# PI3523_EVAL_v2.net
KiCad netlist of a schematic drawn in EAGLE
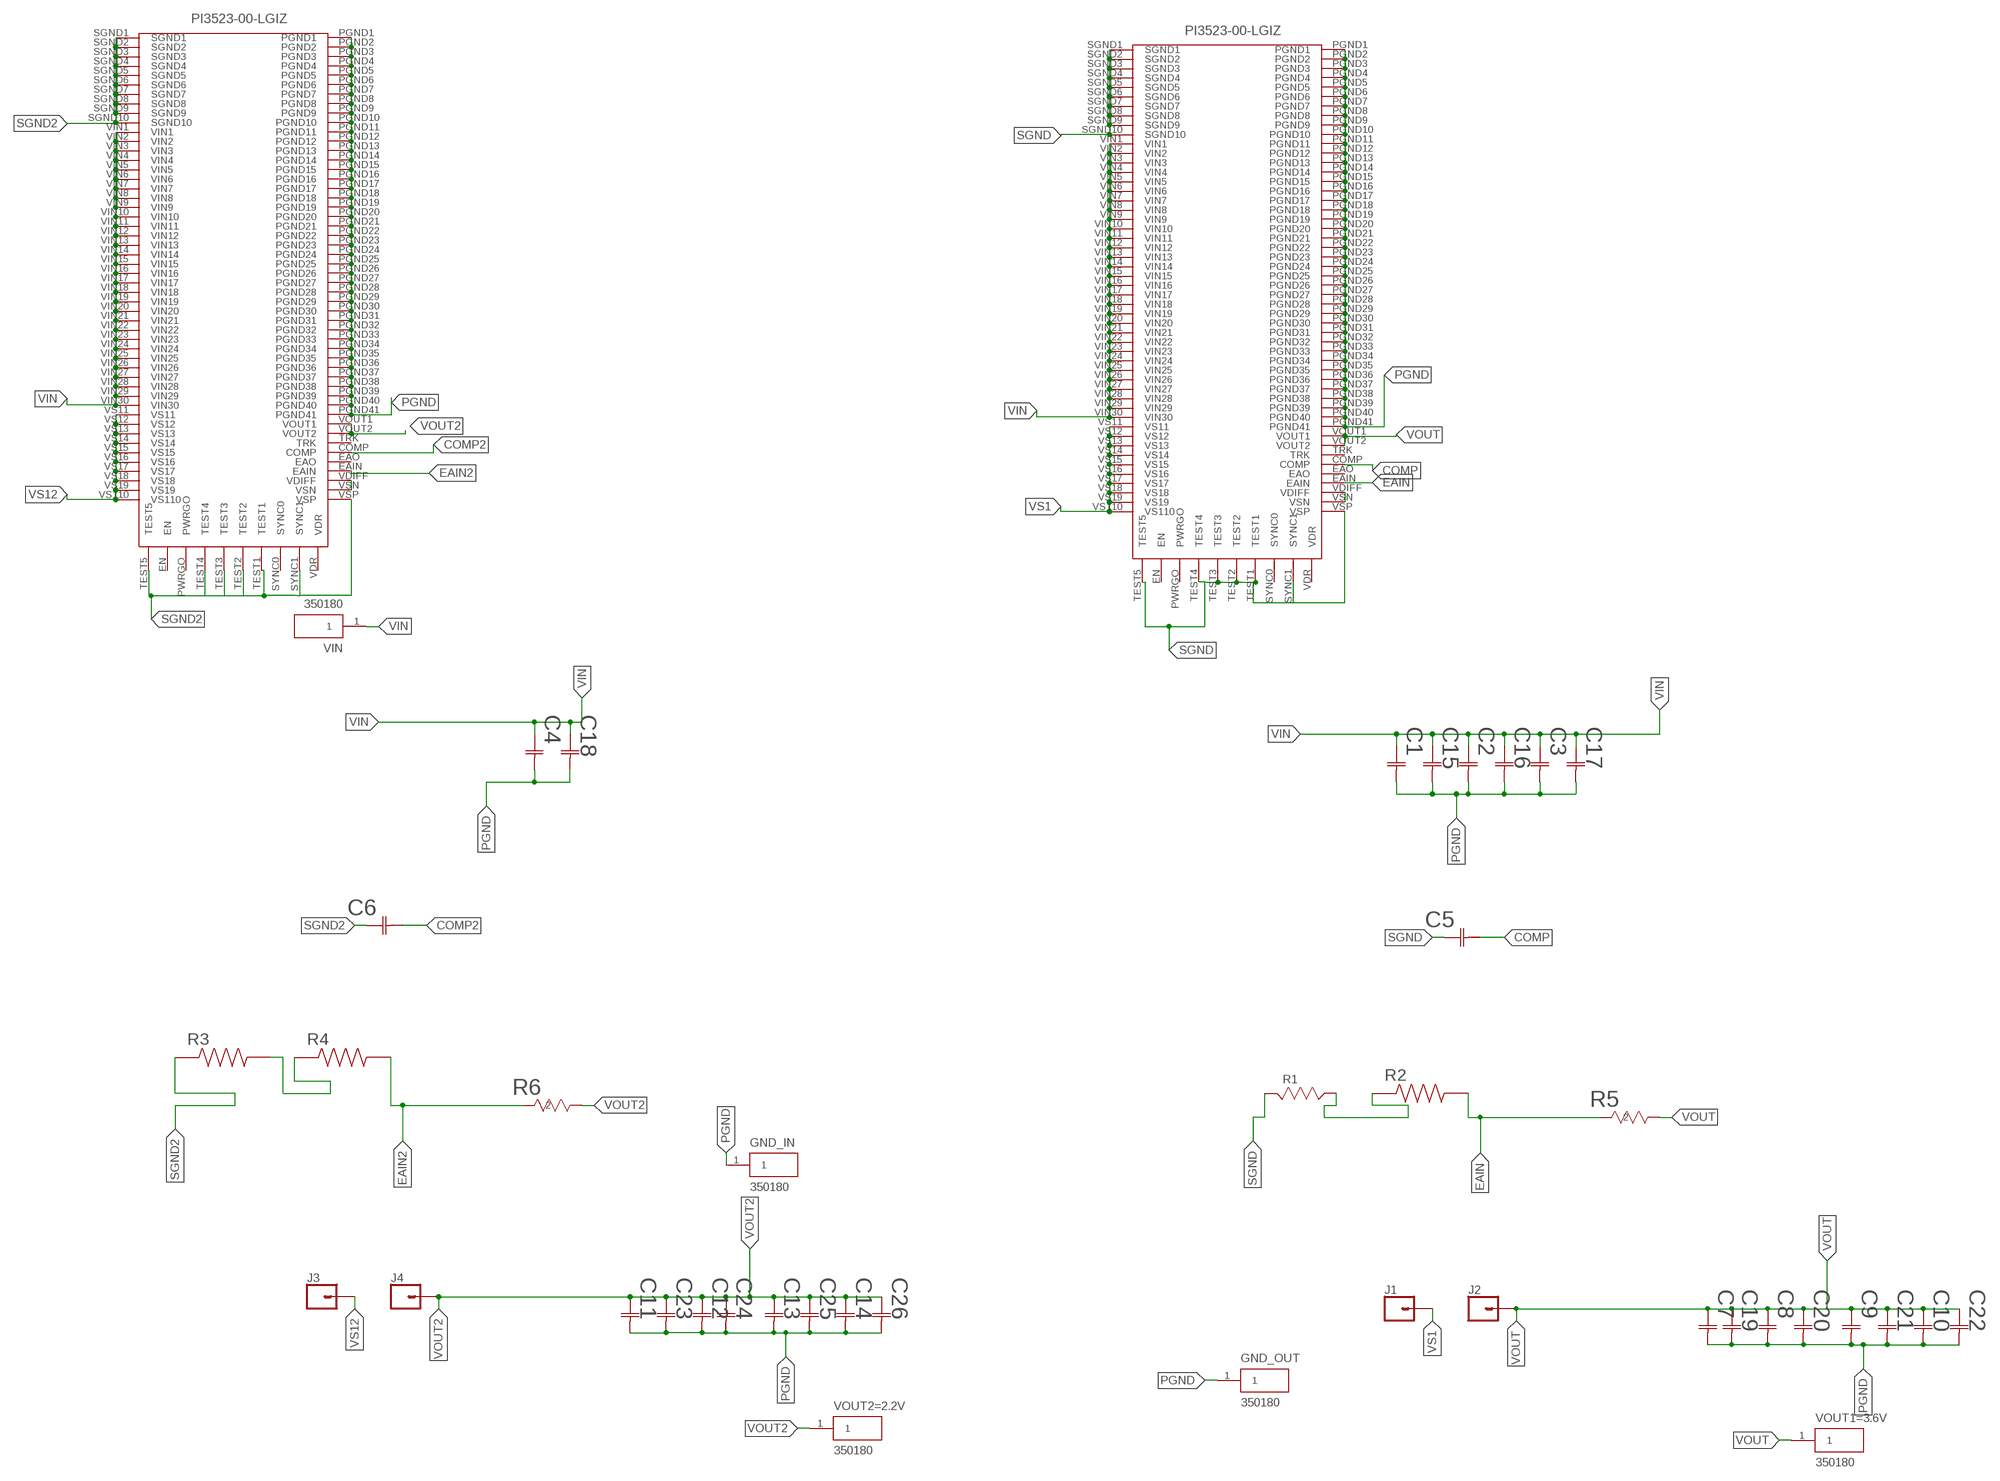
[diagram p0: schematic, sheet 1]

(export (version "E")
  (design (tool "Eeschema 10.0.6"))
  (components
    (comp (ref "C1")
      (value "GRM32ER72A225KA35L")
      (footprint "eagle-import:G-32_MUR")
      (fields (field (name "COPYRIGHT") "Copyright (C) 2015 Accelerated Designs. All rights reserved"))
      (libsource (lib "eagle-import") (part "GRM32ER72A225KA35L"))
    )
    (comp (ref "C2")
      (value "GRM32ER72A225KA35L")
      (footprint "eagle-import:G-32_MUR")
      (fields (field (name "COPYRIGHT") "Copyright (C) 2015 Accelerated Designs. All rights reserved"))
      (libsource (lib "eagle-import") (part "GRM32ER72A225KA35L"))
    )
    (comp (ref "C3")
      (value "GRM32ER72A225KA35L")
      (footprint "eagle-import:G-32_MUR")
      (fields (field (name "COPYRIGHT") "Copyright (C) 2015 Accelerated Designs. All rights reserved"))
      (libsource (lib "eagle-import") (part "GRM32ER72A225KA35L"))
    )
    (comp (ref "C4")
      (value "GRM32ER72A225KA35L")
      (footprint "eagle-import:G-32_MUR")
      (fields (field (name "COPYRIGHT") "Copyright (C) 2015 Accelerated Designs. All rights reserved"))
      (libsource (lib "eagle-import") (part "GRM32ER72A225KA35L"))
    )
    (comp (ref "C5")
      (value "C1608C0G2A472J080AC")
      (footprint "eagle-import:CAP_C1608_TDK")
      (fields (field (name "COPYRIGHT") "Copyright (C) 2018 Accelerated Designs. All rights reserved"))
      (libsource (lib "eagle-import") (part "C1608C0G2A472J080AC"))
    )
    (comp (ref "C6")
      (value "C1608C0G2A472J080AC")
      (footprint "eagle-import:CAP_C1608_TDK")
      (fields (field (name "COPYRIGHT") "Copyright (C) 2018 Accelerated Designs. All rights reserved"))
      (libsource (lib "eagle-import") (part "C1608C0G2A472J080AC"))
    )
    (comp (ref "C7")
      (value "GRM32EC80J107ME20L")
      (footprint "eagle-import:G-32_MUR")
      (fields (field (name "COPYRIGHT") "Copyright (C) 2015 Accelerated Designs. All rights reserved"))
      (libsource (lib "eagle-import") (part "GRM32EC80J107ME20L"))
    )
    (comp (ref "C8")
      (value "GRM32EC80J107ME20L")
      (footprint "eagle-import:G-32_MUR")
      (fields (field (name "COPYRIGHT") "Copyright (C) 2015 Accelerated Designs. All rights reserved"))
      (libsource (lib "eagle-import") (part "GRM32EC80J107ME20L"))
    )
    (comp (ref "C9")
      (value "GRM32EC80J107ME20L")
      (footprint "eagle-import:G-32_MUR")
      (fields (field (name "COPYRIGHT") "Copyright (C) 2015 Accelerated Designs. All rights reserved"))
      (libsource (lib "eagle-import") (part "GRM32EC80J107ME20L"))
    )
    (comp (ref "C10")
      (value "GRM32EC80J107ME20L")
      (footprint "eagle-import:G-32_MUR")
      (fields (field (name "COPYRIGHT") "Copyright (C) 2015 Accelerated Designs. All rights reserved"))
      (libsource (lib "eagle-import") (part "GRM32EC80J107ME20L"))
    )
    (comp (ref "C11")
      (value "GRM32EC80J107ME20L")
      (footprint "eagle-import:G-32_MUR")
      (fields (field (name "COPYRIGHT") "Copyright (C) 2015 Accelerated Designs. All rights reserved"))
      (libsource (lib "eagle-import") (part "GRM32EC80J107ME20L"))
    )
    (comp (ref "C12")
      (value "GRM32EC80J107ME20L")
      (footprint "eagle-import:G-32_MUR")
      (fields (field (name "COPYRIGHT") "Copyright (C) 2015 Accelerated Designs. All rights reserved"))
      (libsource (lib "eagle-import") (part "GRM32EC80J107ME20L"))
    )
    (comp (ref "C13")
      (value "GRM32EC80J107ME20L")
      (footprint "eagle-import:G-32_MUR")
      (fields (field (name "COPYRIGHT") "Copyright (C) 2015 Accelerated Designs. All rights reserved"))
      (libsource (lib "eagle-import") (part "GRM32EC80J107ME20L"))
    )
    (comp (ref "C14")
      (value "GRM32EC80J107ME20L")
      (footprint "eagle-import:G-32_MUR")
      (fields (field (name "COPYRIGHT") "Copyright (C) 2015 Accelerated Designs. All rights reserved"))
      (libsource (lib "eagle-import") (part "GRM32EC80J107ME20L"))
    )
    (comp (ref "C15")
      (value "GRM32ER72A225KA35L")
      (footprint "eagle-import:G-32_MUR")
      (fields (field (name "COPYRIGHT") "Copyright (C) 2015 Accelerated Designs. All rights reserved"))
      (libsource (lib "eagle-import") (part "GRM32ER72A225KA35L"))
    )
    (comp (ref "C16")
      (value "GRM32ER72A225KA35L")
      (footprint "eagle-import:G-32_MUR")
      (fields (field (name "COPYRIGHT") "Copyright (C) 2015 Accelerated Designs. All rights reserved"))
      (libsource (lib "eagle-import") (part "GRM32ER72A225KA35L"))
    )
    (comp (ref "C17")
      (value "GRM32ER72A225KA35L")
      (footprint "eagle-import:G-32_MUR")
      (fields (field (name "COPYRIGHT") "Copyright (C) 2015 Accelerated Designs. All rights reserved"))
      (libsource (lib "eagle-import") (part "GRM32ER72A225KA35L"))
    )
    (comp (ref "C18")
      (value "GRM32ER72A225KA35L")
      (footprint "eagle-import:G-32_MUR")
      (fields (field (name "COPYRIGHT") "Copyright (C) 2015 Accelerated Designs. All rights reserved"))
      (libsource (lib "eagle-import") (part "GRM32ER72A225KA35L"))
    )
    (comp (ref "C19")
      (value "GRM32EC80J107ME20L")
      (footprint "eagle-import:G-32_MUR")
      (fields (field (name "COPYRIGHT") "Copyright (C) 2015 Accelerated Designs. All rights reserved"))
      (libsource (lib "eagle-import") (part "GRM32EC80J107ME20L"))
    )
    (comp (ref "C20")
      (value "GRM32EC80J107ME20L")
      (footprint "eagle-import:G-32_MUR")
      (fields (field (name "COPYRIGHT") "Copyright (C) 2015 Accelerated Designs. All rights reserved"))
      (libsource (lib "eagle-import") (part "GRM32EC80J107ME20L"))
    )
    (comp (ref "C21")
      (value "GRM32EC80J107ME20L")
      (footprint "eagle-import:G-32_MUR")
      (fields (field (name "COPYRIGHT") "Copyright (C) 2015 Accelerated Designs. All rights reserved"))
      (libsource (lib "eagle-import") (part "GRM32EC80J107ME20L"))
    )
    (comp (ref "C22")
      (value "GRM32EC80J107ME20L")
      (footprint "eagle-import:G-32_MUR")
      (fields (field (name "COPYRIGHT") "Copyright (C) 2015 Accelerated Designs. All rights reserved"))
      (libsource (lib "eagle-import") (part "GRM32EC80J107ME20L"))
    )
    (comp (ref "C23")
      (value "GRM32EC80J107ME20L")
      (footprint "eagle-import:G-32_MUR")
      (fields (field (name "COPYRIGHT") "Copyright (C) 2015 Accelerated Designs. All rights reserved"))
      (libsource (lib "eagle-import") (part "GRM32EC80J107ME20L"))
    )
    (comp (ref "C24")
      (value "GRM32EC80J107ME20L")
      (footprint "eagle-import:G-32_MUR")
      (fields (field (name "COPYRIGHT") "Copyright (C) 2015 Accelerated Designs. All rights reserved"))
      (libsource (lib "eagle-import") (part "GRM32EC80J107ME20L"))
    )
    (comp (ref "C25")
      (value "GRM32EC80J107ME20L")
      (footprint "eagle-import:G-32_MUR")
      (fields (field (name "COPYRIGHT") "Copyright (C) 2015 Accelerated Designs. All rights reserved"))
      (libsource (lib "eagle-import") (part "GRM32EC80J107ME20L"))
    )
    (comp (ref "C26")
      (value "GRM32EC80J107ME20L")
      (footprint "eagle-import:G-32_MUR")
      (fields (field (name "COPYRIGHT") "Copyright (C) 2015 Accelerated Designs. All rights reserved"))
      (libsource (lib "eagle-import") (part "GRM32EC80J107ME20L"))
    )
    (comp (ref "GND_IN")
      (value "350180")
      (footprint "eagle-import:TE_350180")
      (fields (field (name "MF") "TE Connectivity"))
      (libsource (lib "eagle-import") (part "350180"))
    )
    (comp (ref "GND_OUT")
      (value "350180")
      (footprint "eagle-import:TE_350180")
      (fields (field (name "MF") "TE Connectivity"))
      (libsource (lib "eagle-import") (part "350180"))
    )
    (comp (ref "J1")
      (value "CONN_01")
      (footprint "eagle-import:1X01")
      (libsource (lib "eagle-import") (part "CONN_01"))
    )
    (comp (ref "J2")
      (value "CONN_01")
      (footprint "eagle-import:1X01")
      (libsource (lib "eagle-import") (part "CONN_01"))
    )
    (comp (ref "J3")
      (value "CONN_01")
      (footprint "eagle-import:1X01")
      (libsource (lib "eagle-import") (part "CONN_01"))
    )
    (comp (ref "J4")
      (value "CONN_01")
      (footprint "eagle-import:1X01")
      (libsource (lib "eagle-import") (part "CONN_01"))
    )
    (comp (ref "R1")
      (value "ERJ-3GEY0R00V")
      (footprint "eagle-import:RESC1608X55")
      (fields (field (name "MF") "Panasonic Electronic"))
      (libsource (lib "eagle-import") (part "ERJ-3GEY0R00V"))
    )
    (comp (ref "R2")
      (value "ERA-3APB911V")
      (footprint "eagle-import:RESC1608X55N")
      (fields (field (name "MF") "Panasonic"))
      (libsource (lib "eagle-import") (part "ERA-3APB911V"))
    )
    (comp (ref "R3")
      (value "ERJ-3BQJ3R6V")
      (footprint "eagle-import:RESC1608X55N")
      (fields (field (name "MF") "Panasonic"))
      (libsource (lib "eagle-import") (part "ERJ-3BQJ3R6V"))
    )
    (comp (ref "R4")
      (value "ERA-3AEB1961V")
      (footprint "eagle-import:RESC1608X55N")
      (fields (field (name "MF") "Panasonic"))
      (libsource (lib "eagle-import") (part "ERA-3AEB1961V"))
    )
    (comp (ref "R5")
      (value "RT0603BRE072K4L")
      (footprint "eagle-import:RC0603N_YAG")
      (libsource (lib "eagle-import") (part "RT0603BRE072K4L"))
    )
    (comp (ref "R6")
      (value "RT0603BRE072K4L")
      (footprint "eagle-import:RC0603N_YAG")
      (libsource (lib "eagle-import") (part "RT0603BRE072K4L"))
    )
    (comp (ref "U$1")
      (value "PI3523-00-LGIZ")
      (footprint "eagle-import:PI3523-00-LGIZ")
      (libsource (lib "eagle-import") (part "PI3523-00-LGIZ"))
    )
    (comp (ref "U$2")
      (value "PI3523-00-LGIZ")
      (footprint "eagle-import:PI3523-00-LGIZ")
      (libsource (lib "eagle-import") (part "PI3523-00-LGIZ"))
    )
    (comp (ref "VIN")
      (value "350180")
      (footprint "eagle-import:TE_350180")
      (fields (field (name "MF") "TE Connectivity"))
      (libsource (lib "eagle-import") (part "350180"))
    )
    (comp (ref "VOUT1=3.6V")
      (value "350180")
      (footprint "eagle-import:TE_350180")
      (fields (field (name "MF") "TE Connectivity"))
      (libsource (lib "eagle-import") (part "350180"))
    )
    (comp (ref "VOUT2=2.2V")
      (value "350180")
      (footprint "eagle-import:TE_350180")
      (fields (field (name "MF") "TE Connectivity"))
      (libsource (lib "eagle-import") (part "350180"))
    )
  )
  (nets
    (net (code "1") (name "COMP") (class "Default")
      (node (ref "C5") (pin "2") (pinfunction "2_2") (pintype "passive"))
      (node (ref "U$2") (pin "COMP") (pinfunction "COMP_COMP") (pintype "bidirectional"))
    )
    (net (code "2") (name "COMP2") (class "Default")
      (node (ref "C6") (pin "2") (pinfunction "2_2") (pintype "passive"))
      (node (ref "U$1") (pin "COMP") (pinfunction "COMP_COMP") (pintype "bidirectional"))
    )
    (net (code "3") (name "EAIN") (class "Default")
      (node (ref "R2") (pin "2") (pinfunction "2_2") (pintype "passive"))
      (node (ref "R5") (pin "2") (pinfunction "2_2") (pintype "passive"))
      (node (ref "U$2") (pin "EAIN") (pinfunction "EAIN_EAIN") (pintype "bidirectional"))
    )
    (net (code "4") (name "EAIN2") (class "Default")
      (node (ref "R4") (pin "2") (pinfunction "2_2") (pintype "passive"))
      (node (ref "R6") (pin "2") (pinfunction "2_2") (pintype "passive"))
      (node (ref "U$1") (pin "EAIN") (pinfunction "EAIN_EAIN") (pintype "bidirectional"))
    )
    (net (code "5") (name "Net-(R1-Pad2)") (class "Default")
      (node (ref "R1") (pin "2") (pinfunction "2_2") (pintype "passive"))
      (node (ref "R2") (pin "1") (pinfunction "1_1") (pintype "passive"))
    )
    (net (code "6") (name "Net-(R3-Pad2)") (class "Default")
      (node (ref "R3") (pin "2") (pinfunction "2_2") (pintype "passive"))
      (node (ref "R4") (pin "1") (pinfunction "1_1") (pintype "passive"))
    )
    (net (code "7") (name "Net-(U$1-PadVDIFF)") (class "Default")
      (node (ref "U$1") (pin "VDIFF") (pinfunction "VDIFF_VDIFF") (pintype "bidirectional"))
      (node (ref "U$1") (pin "VSN") (pinfunction "VSN_VSN") (pintype "bidirectional"))
    )
    (net (code "8") (name "Net-(U$2-PadVDIFF)") (class "Default")
      (node (ref "U$2") (pin "VDIFF") (pinfunction "VDIFF_VDIFF") (pintype "bidirectional"))
      (node (ref "U$2") (pin "VSN") (pinfunction "VSN_VSN") (pintype "bidirectional"))
    )
    (net (code "9") (name "PGND") (class "Default")
      (node (ref "C1") (pin "2") (pinfunction "2_2") (pintype "passive"))
      (node (ref "C10") (pin "2") (pinfunction "2_2") (pintype "passive"))
      (node (ref "C11") (pin "2") (pinfunction "2_2") (pintype "passive"))
      (node (ref "C12") (pin "2") (pinfunction "2_2") (pintype "passive"))
      (node (ref "C13") (pin "2") (pinfunction "2_2") (pintype "passive"))
      (node (ref "C14") (pin "2") (pinfunction "2_2") (pintype "passive"))
      (node (ref "C15") (pin "2") (pinfunction "2_2") (pintype "passive"))
      (node (ref "C16") (pin "2") (pinfunction "2_2") (pintype "passive"))
      (node (ref "C17") (pin "2") (pinfunction "2_2") (pintype "passive"))
      (node (ref "C18") (pin "2") (pinfunction "2_2") (pintype "passive"))
      (node (ref "C19") (pin "2") (pinfunction "2_2") (pintype "passive"))
      (node (ref "C2") (pin "2") (pinfunction "2_2") (pintype "passive"))
      (node (ref "C20") (pin "2") (pinfunction "2_2") (pintype "passive"))
      (node (ref "C21") (pin "2") (pinfunction "2_2") (pintype "passive"))
      (node (ref "C22") (pin "2") (pinfunction "2_2") (pintype "passive"))
      (node (ref "C23") (pin "2") (pinfunction "2_2") (pintype "passive"))
      (node (ref "C24") (pin "2") (pinfunction "2_2") (pintype "passive"))
      (node (ref "C25") (pin "2") (pinfunction "2_2") (pintype "passive"))
      (node (ref "C26") (pin "2") (pinfunction "2_2") (pintype "passive"))
      (node (ref "C3") (pin "2") (pinfunction "2_2") (pintype "passive"))
      (node (ref "C4") (pin "2") (pinfunction "2_2") (pintype "passive"))
      (node (ref "C7") (pin "2") (pinfunction "2_2") (pintype "passive"))
      (node (ref "C8") (pin "2") (pinfunction "2_2") (pintype "passive"))
      (node (ref "C9") (pin "2") (pinfunction "2_2") (pintype "passive"))
      (node (ref "GND_IN") (pin "1") (pinfunction "1_1") (pintype "passive"))
      (node (ref "GND_OUT") (pin "1") (pinfunction "1_1") (pintype "passive"))
      (node (ref "U$1") (pin "PGND1") (pinfunction "PGND1_PGND1") (pintype "bidirectional"))
      (node (ref "U$1") (pin "PGND10") (pinfunction "PGND10_PGND10") (pintype "bidirectional"))
      (node (ref "U$1") (pin "PGND11") (pinfunction "PGND11_PGND11") (pintype "bidirectional"))
      (node (ref "U$1") (pin "PGND12") (pinfunction "PGND12_PGND12") (pintype "bidirectional"))
      (node (ref "U$1") (pin "PGND13") (pinfunction "PGND13_PGND13") (pintype "bidirectional"))
      (node (ref "U$1") (pin "PGND14") (pinfunction "PGND14_PGND14") (pintype "bidirectional"))
      (node (ref "U$1") (pin "PGND15") (pinfunction "PGND15_PGND15") (pintype "bidirectional"))
      (node (ref "U$1") (pin "PGND16") (pinfunction "PGND16_PGND16") (pintype "bidirectional"))
      (node (ref "U$1") (pin "PGND17") (pinfunction "PGND17_PGND17") (pintype "bidirectional"))
      (node (ref "U$1") (pin "PGND18") (pinfunction "PGND18_PGND18") (pintype "bidirectional"))
      (node (ref "U$1") (pin "PGND19") (pinfunction "PGND19_PGND19") (pintype "bidirectional"))
      (node (ref "U$1") (pin "PGND2") (pinfunction "PGND2_PGND2") (pintype "bidirectional"))
      (node (ref "U$1") (pin "PGND20") (pinfunction "PGND20_PGND20") (pintype "bidirectional"))
      (node (ref "U$1") (pin "PGND21") (pinfunction "PGND21_PGND21") (pintype "bidirectional"))
      (node (ref "U$1") (pin "PGND22") (pinfunction "PGND22_PGND22") (pintype "bidirectional"))
      (node (ref "U$1") (pin "PGND23") (pinfunction "PGND23_PGND23") (pintype "bidirectional"))
      (node (ref "U$1") (pin "PGND24") (pinfunction "PGND24_PGND24") (pintype "bidirectional"))
      (node (ref "U$1") (pin "PGND25") (pinfunction "PGND25_PGND25") (pintype "bidirectional"))
      (node (ref "U$1") (pin "PGND26") (pinfunction "PGND26_PGND26") (pintype "bidirectional"))
      (node (ref "U$1") (pin "PGND27") (pinfunction "PGND27_PGND27") (pintype "bidirectional"))
      (node (ref "U$1") (pin "PGND28") (pinfunction "PGND28_PGND28") (pintype "bidirectional"))
      (node (ref "U$1") (pin "PGND29") (pinfunction "PGND29_PGND29") (pintype "bidirectional"))
      (node (ref "U$1") (pin "PGND3") (pinfunction "PGND3_PGND3") (pintype "bidirectional"))
      (node (ref "U$1") (pin "PGND30") (pinfunction "PGND30_PGND30") (pintype "bidirectional"))
      (node (ref "U$1") (pin "PGND31") (pinfunction "PGND31_PGND31") (pintype "bidirectional"))
      (node (ref "U$1") (pin "PGND32") (pinfunction "PGND32_PGND32") (pintype "bidirectional"))
      (node (ref "U$1") (pin "PGND33") (pinfunction "PGND33_PGND33") (pintype "bidirectional"))
      (node (ref "U$1") (pin "PGND34") (pinfunction "PGND34_PGND34") (pintype "bidirectional"))
      (node (ref "U$1") (pin "PGND35") (pinfunction "PGND35_PGND35") (pintype "bidirectional"))
      (node (ref "U$1") (pin "PGND36") (pinfunction "PGND36_PGND36") (pintype "bidirectional"))
      (node (ref "U$1") (pin "PGND37") (pinfunction "PGND37_PGND37") (pintype "bidirectional"))
      (node (ref "U$1") (pin "PGND38") (pinfunction "PGND38_PGND38") (pintype "bidirectional"))
      (node (ref "U$1") (pin "PGND39") (pinfunction "PGND39_PGND39") (pintype "bidirectional"))
      (node (ref "U$1") (pin "PGND4") (pinfunction "PGND4_PGND4") (pintype "bidirectional"))
      (node (ref "U$1") (pin "PGND40") (pinfunction "PGND40_PGND40") (pintype "bidirectional"))
      (node (ref "U$1") (pin "PGND41") (pinfunction "PGND41_PGND41") (pintype "bidirectional"))
      (node (ref "U$1") (pin "PGND5") (pinfunction "PGND5_PGND5") (pintype "bidirectional"))
      (node (ref "U$1") (pin "PGND6") (pinfunction "PGND6_PGND6") (pintype "bidirectional"))
      (node (ref "U$1") (pin "PGND7") (pinfunction "PGND7_PGND7") (pintype "bidirectional"))
      (node (ref "U$1") (pin "PGND8") (pinfunction "PGND8_PGND8") (pintype "bidirectional"))
      (node (ref "U$1") (pin "PGND9") (pinfunction "PGND9_PGND9") (pintype "bidirectional"))
      (node (ref "U$2") (pin "PGND1") (pinfunction "PGND1_PGND1") (pintype "bidirectional"))
      (node (ref "U$2") (pin "PGND10") (pinfunction "PGND10_PGND10") (pintype "bidirectional"))
      (node (ref "U$2") (pin "PGND11") (pinfunction "PGND11_PGND11") (pintype "bidirectional"))
      (node (ref "U$2") (pin "PGND12") (pinfunction "PGND12_PGND12") (pintype "bidirectional"))
      (node (ref "U$2") (pin "PGND13") (pinfunction "PGND13_PGND13") (pintype "bidirectional"))
      (node (ref "U$2") (pin "PGND14") (pinfunction "PGND14_PGND14") (pintype "bidirectional"))
      (node (ref "U$2") (pin "PGND15") (pinfunction "PGND15_PGND15") (pintype "bidirectional"))
      (node (ref "U$2") (pin "PGND16") (pinfunction "PGND16_PGND16") (pintype "bidirectional"))
      (node (ref "U$2") (pin "PGND17") (pinfunction "PGND17_PGND17") (pintype "bidirectional"))
      (node (ref "U$2") (pin "PGND18") (pinfunction "PGND18_PGND18") (pintype "bidirectional"))
      (node (ref "U$2") (pin "PGND19") (pinfunction "PGND19_PGND19") (pintype "bidirectional"))
      (node (ref "U$2") (pin "PGND2") (pinfunction "PGND2_PGND2") (pintype "bidirectional"))
      (node (ref "U$2") (pin "PGND20") (pinfunction "PGND20_PGND20") (pintype "bidirectional"))
      (node (ref "U$2") (pin "PGND21") (pinfunction "PGND21_PGND21") (pintype "bidirectional"))
      (node (ref "U$2") (pin "PGND22") (pinfunction "PGND22_PGND22") (pintype "bidirectional"))
      (node (ref "U$2") (pin "PGND23") (pinfunction "PGND23_PGND23") (pintype "bidirectional"))
      (node (ref "U$2") (pin "PGND24") (pinfunction "PGND24_PGND24") (pintype "bidirectional"))
      (node (ref "U$2") (pin "PGND25") (pinfunction "PGND25_PGND25") (pintype "bidirectional"))
      (node (ref "U$2") (pin "PGND26") (pinfunction "PGND26_PGND26") (pintype "bidirectional"))
      (node (ref "U$2") (pin "PGND27") (pinfunction "PGND27_PGND27") (pintype "bidirectional"))
      (node (ref "U$2") (pin "PGND28") (pinfunction "PGND28_PGND28") (pintype "bidirectional"))
      (node (ref "U$2") (pin "PGND29") (pinfunction "PGND29_PGND29") (pintype "bidirectional"))
      (node (ref "U$2") (pin "PGND3") (pinfunction "PGND3_PGND3") (pintype "bidirectional"))
      (node (ref "U$2") (pin "PGND30") (pinfunction "PGND30_PGND30") (pintype "bidirectional"))
      (node (ref "U$2") (pin "PGND31") (pinfunction "PGND31_PGND31") (pintype "bidirectional"))
      (node (ref "U$2") (pin "PGND32") (pinfunction "PGND32_PGND32") (pintype "bidirectional"))
      (node (ref "U$2") (pin "PGND33") (pinfunction "PGND33_PGND33") (pintype "bidirectional"))
      (node (ref "U$2") (pin "PGND34") (pinfunction "PGND34_PGND34") (pintype "bidirectional"))
      (node (ref "U$2") (pin "PGND35") (pinfunction "PGND35_PGND35") (pintype "bidirectional"))
      (node (ref "U$2") (pin "PGND36") (pinfunction "PGND36_PGND36") (pintype "bidirectional"))
      (node (ref "U$2") (pin "PGND37") (pinfunction "PGND37_PGND37") (pintype "bidirectional"))
      (node (ref "U$2") (pin "PGND38") (pinfunction "PGND38_PGND38") (pintype "bidirectional"))
      (node (ref "U$2") (pin "PGND39") (pinfunction "PGND39_PGND39") (pintype "bidirectional"))
      (node (ref "U$2") (pin "PGND4") (pinfunction "PGND4_PGND4") (pintype "bidirectional"))
      (node (ref "U$2") (pin "PGND40") (pinfunction "PGND40_PGND40") (pintype "bidirectional"))
      (node (ref "U$2") (pin "PGND41") (pinfunction "PGND41_PGND41") (pintype "bidirectional"))
      (node (ref "U$2") (pin "PGND5") (pinfunction "PGND5_PGND5") (pintype "bidirectional"))
      (node (ref "U$2") (pin "PGND6") (pinfunction "PGND6_PGND6") (pintype "bidirectional"))
      (node (ref "U$2") (pin "PGND7") (pinfunction "PGND7_PGND7") (pintype "bidirectional"))
      (node (ref "U$2") (pin "PGND8") (pinfunction "PGND8_PGND8") (pintype "bidirectional"))
      (node (ref "U$2") (pin "PGND9") (pinfunction "PGND9_PGND9") (pintype "bidirectional"))
    )
    (net (code "10") (name "SGND") (class "Default")
      (node (ref "C5") (pin "1") (pinfunction "1_1") (pintype "passive"))
      (node (ref "R1") (pin "1") (pinfunction "1_1") (pintype "passive"))
      (node (ref "U$2") (pin "SGND1") (pinfunction "SGND1_SGND1") (pintype "bidirectional"))
      (node (ref "U$2") (pin "SGND10") (pinfunction "SGND10_SGND10") (pintype "bidirectional"))
      (node (ref "U$2") (pin "SGND2") (pinfunction "SGND2_SGND2") (pintype "bidirectional"))
      (node (ref "U$2") (pin "SGND3") (pinfunction "SGND3_SGND3") (pintype "bidirectional"))
      (node (ref "U$2") (pin "SGND4") (pinfunction "SGND4_SGND4") (pintype "bidirectional"))
      (node (ref "U$2") (pin "SGND5") (pinfunction "SGND5_SGND5") (pintype "bidirectional"))
      (node (ref "U$2") (pin "SGND6") (pinfunction "SGND6_SGND6") (pintype "bidirectional"))
      (node (ref "U$2") (pin "SGND7") (pinfunction "SGND7_SGND7") (pintype "bidirectional"))
      (node (ref "U$2") (pin "SGND8") (pinfunction "SGND8_SGND8") (pintype "bidirectional"))
      (node (ref "U$2") (pin "SGND9") (pinfunction "SGND9_SGND9") (pintype "bidirectional"))
      (node (ref "U$2") (pin "SYNC1") (pinfunction "SYNC1_SYNC1") (pintype "bidirectional"))
      (node (ref "U$2") (pin "TEST1") (pinfunction "TEST1_TEST1") (pintype "bidirectional"))
      (node (ref "U$2") (pin "TEST2") (pinfunction "TEST2_TEST2") (pintype "bidirectional"))
      (node (ref "U$2") (pin "TEST3") (pinfunction "TEST3_TEST3") (pintype "bidirectional"))
      (node (ref "U$2") (pin "TEST4") (pinfunction "TEST4_TEST4") (pintype "bidirectional"))
      (node (ref "U$2") (pin "TEST5") (pinfunction "TEST5_TEST5") (pintype "bidirectional"))
      (node (ref "U$2") (pin "VSP") (pinfunction "VSP_VSP") (pintype "bidirectional"))
    )
    (net (code "11") (name "SGND2") (class "Default")
      (node (ref "C6") (pin "1") (pinfunction "1_1") (pintype "passive"))
      (node (ref "R3") (pin "1") (pinfunction "1_1") (pintype "passive"))
      (node (ref "U$1") (pin "SGND1") (pinfunction "SGND1_SGND1") (pintype "bidirectional"))
      (node (ref "U$1") (pin "SGND10") (pinfunction "SGND10_SGND10") (pintype "bidirectional"))
      (node (ref "U$1") (pin "SGND2") (pinfunction "SGND2_SGND2") (pintype "bidirectional"))
      (node (ref "U$1") (pin "SGND3") (pinfunction "SGND3_SGND3") (pintype "bidirectional"))
      (node (ref "U$1") (pin "SGND4") (pinfunction "SGND4_SGND4") (pintype "bidirectional"))
      (node (ref "U$1") (pin "SGND5") (pinfunction "SGND5_SGND5") (pintype "bidirectional"))
      (node (ref "U$1") (pin "SGND6") (pinfunction "SGND6_SGND6") (pintype "bidirectional"))
      (node (ref "U$1") (pin "SGND7") (pinfunction "SGND7_SGND7") (pintype "bidirectional"))
      (node (ref "U$1") (pin "SGND8") (pinfunction "SGND8_SGND8") (pintype "bidirectional"))
      (node (ref "U$1") (pin "SGND9") (pinfunction "SGND9_SGND9") (pintype "bidirectional"))
      (node (ref "U$1") (pin "SYNC1") (pinfunction "SYNC1_SYNC1") (pintype "bidirectional"))
      (node (ref "U$1") (pin "TEST1") (pinfunction "TEST1_TEST1") (pintype "bidirectional"))
      (node (ref "U$1") (pin "TEST2") (pinfunction "TEST2_TEST2") (pintype "bidirectional"))
      (node (ref "U$1") (pin "TEST3") (pinfunction "TEST3_TEST3") (pintype "bidirectional"))
      (node (ref "U$1") (pin "TEST4") (pinfunction "TEST4_TEST4") (pintype "bidirectional"))
      (node (ref "U$1") (pin "TEST5") (pinfunction "TEST5_TEST5") (pintype "bidirectional"))
      (node (ref "U$1") (pin "VSP") (pinfunction "VSP_VSP") (pintype "bidirectional"))
    )
    (net (code "12") (name "VIN") (class "Default")
      (node (ref "C1") (pin "1") (pinfunction "1_1") (pintype "passive"))
      (node (ref "C15") (pin "1") (pinfunction "1_1") (pintype "passive"))
      (node (ref "C16") (pin "1") (pinfunction "1_1") (pintype "passive"))
      (node (ref "C17") (pin "1") (pinfunction "1_1") (pintype "passive"))
      (node (ref "C18") (pin "1") (pinfunction "1_1") (pintype "passive"))
      (node (ref "C2") (pin "1") (pinfunction "1_1") (pintype "passive"))
      (node (ref "C3") (pin "1") (pinfunction "1_1") (pintype "passive"))
      (node (ref "C4") (pin "1") (pinfunction "1_1") (pintype "passive"))
      (node (ref "U$1") (pin "VIN1") (pinfunction "VIN1_VIN1") (pintype "bidirectional"))
      (node (ref "U$1") (pin "VIN10") (pinfunction "VIN10_VIN10") (pintype "bidirectional"))
      (node (ref "U$1") (pin "VIN11") (pinfunction "VIN11_VIN11") (pintype "bidirectional"))
      (node (ref "U$1") (pin "VIN12") (pinfunction "VIN12_VIN12") (pintype "bidirectional"))
      (node (ref "U$1") (pin "VIN13") (pinfunction "VIN13_VIN13") (pintype "bidirectional"))
      (node (ref "U$1") (pin "VIN14") (pinfunction "VIN14_VIN14") (pintype "bidirectional"))
      (node (ref "U$1") (pin "VIN15") (pinfunction "VIN15_VIN15") (pintype "bidirectional"))
      (node (ref "U$1") (pin "VIN16") (pinfunction "VIN16_VIN16") (pintype "bidirectional"))
      (node (ref "U$1") (pin "VIN17") (pinfunction "VIN17_VIN17") (pintype "bidirectional"))
      (node (ref "U$1") (pin "VIN18") (pinfunction "VIN18_VIN18") (pintype "bidirectional"))
      (node (ref "U$1") (pin "VIN19") (pinfunction "VIN19_VIN19") (pintype "bidirectional"))
      (node (ref "U$1") (pin "VIN2") (pinfunction "VIN2_VIN2") (pintype "bidirectional"))
      (node (ref "U$1") (pin "VIN20") (pinfunction "VIN20_VIN20") (pintype "bidirectional"))
      (node (ref "U$1") (pin "VIN21") (pinfunction "VIN21_VIN21") (pintype "bidirectional"))
      (node (ref "U$1") (pin "VIN22") (pinfunction "VIN22_VIN22") (pintype "bidirectional"))
      (node (ref "U$1") (pin "VIN23") (pinfunction "VIN23_VIN23") (pintype "bidirectional"))
      (node (ref "U$1") (pin "VIN24") (pinfunction "VIN24_VIN24") (pintype "bidirectional"))
      (node (ref "U$1") (pin "VIN25") (pinfunction "VIN25_VIN25") (pintype "bidirectional"))
      (node (ref "U$1") (pin "VIN26") (pinfunction "VIN26_VIN26") (pintype "bidirectional"))
      (node (ref "U$1") (pin "VIN27") (pinfunction "VIN27_VIN27") (pintype "bidirectional"))
      (node (ref "U$1") (pin "VIN28") (pinfunction "VIN28_VIN28") (pintype "bidirectional"))
      (node (ref "U$1") (pin "VIN29") (pinfunction "VIN29_VIN29") (pintype "bidirectional"))
      (node (ref "U$1") (pin "VIN3") (pinfunction "VIN3_VIN3") (pintype "bidirectional"))
      (node (ref "U$1") (pin "VIN30") (pinfunction "VIN30_VIN30") (pintype "bidirectional"))
      (node (ref "U$1") (pin "VIN4") (pinfunction "VIN4_VIN4") (pintype "bidirectional"))
      (node (ref "U$1") (pin "VIN5") (pinfunction "VIN5_VIN5") (pintype "bidirectional"))
      (node (ref "U$1") (pin "VIN6") (pinfunction "VIN6_VIN6") (pintype "bidirectional"))
      (node (ref "U$1") (pin "VIN7") (pinfunction "VIN7_VIN7") (pintype "bidirectional"))
      (node (ref "U$1") (pin "VIN8") (pinfunction "VIN8_VIN8") (pintype "bidirectional"))
      (node (ref "U$1") (pin "VIN9") (pinfunction "VIN9_VIN9") (pintype "bidirectional"))
      (node (ref "U$2") (pin "VIN1") (pinfunction "VIN1_VIN1") (pintype "bidirectional"))
      (node (ref "U$2") (pin "VIN10") (pinfunction "VIN10_VIN10") (pintype "bidirectional"))
      (node (ref "U$2") (pin "VIN11") (pinfunction "VIN11_VIN11") (pintype "bidirectional"))
      (node (ref "U$2") (pin "VIN12") (pinfunction "VIN12_VIN12") (pintype "bidirectional"))
      (node (ref "U$2") (pin "VIN13") (pinfunction "VIN13_VIN13") (pintype "bidirectional"))
      (node (ref "U$2") (pin "VIN14") (pinfunction "VIN14_VIN14") (pintype "bidirectional"))
      (node (ref "U$2") (pin "VIN15") (pinfunction "VIN15_VIN15") (pintype "bidirectional"))
      (node (ref "U$2") (pin "VIN16") (pinfunction "VIN16_VIN16") (pintype "bidirectional"))
      (node (ref "U$2") (pin "VIN17") (pinfunction "VIN17_VIN17") (pintype "bidirectional"))
      (node (ref "U$2") (pin "VIN18") (pinfunction "VIN18_VIN18") (pintype "bidirectional"))
      (node (ref "U$2") (pin "VIN19") (pinfunction "VIN19_VIN19") (pintype "bidirectional"))
      (node (ref "U$2") (pin "VIN2") (pinfunction "VIN2_VIN2") (pintype "bidirectional"))
      (node (ref "U$2") (pin "VIN20") (pinfunction "VIN20_VIN20") (pintype "bidirectional"))
      (node (ref "U$2") (pin "VIN21") (pinfunction "VIN21_VIN21") (pintype "bidirectional"))
      (node (ref "U$2") (pin "VIN22") (pinfunction "VIN22_VIN22") (pintype "bidirectional"))
      (node (ref "U$2") (pin "VIN23") (pinfunction "VIN23_VIN23") (pintype "bidirectional"))
      (node (ref "U$2") (pin "VIN24") (pinfunction "VIN24_VIN24") (pintype "bidirectional"))
      (node (ref "U$2") (pin "VIN25") (pinfunction "VIN25_VIN25") (pintype "bidirectional"))
      (node (ref "U$2") (pin "VIN26") (pinfunction "VIN26_VIN26") (pintype "bidirectional"))
      (node (ref "U$2") (pin "VIN27") (pinfunction "VIN27_VIN27") (pintype "bidirectional"))
      (node (ref "U$2") (pin "VIN28") (pinfunction "VIN28_VIN28") (pintype "bidirectional"))
      (node (ref "U$2") (pin "VIN29") (pinfunction "VIN29_VIN29") (pintype "bidirectional"))
      (node (ref "U$2") (pin "VIN3") (pinfunction "VIN3_VIN3") (pintype "bidirectional"))
      (node (ref "U$2") (pin "VIN30") (pinfunction "VIN30_VIN30") (pintype "bidirectional"))
      (node (ref "U$2") (pin "VIN4") (pinfunction "VIN4_VIN4") (pintype "bidirectional"))
      (node (ref "U$2") (pin "VIN5") (pinfunction "VIN5_VIN5") (pintype "bidirectional"))
      (node (ref "U$2") (pin "VIN6") (pinfunction "VIN6_VIN6") (pintype "bidirectional"))
      (node (ref "U$2") (pin "VIN7") (pinfunction "VIN7_VIN7") (pintype "bidirectional"))
      (node (ref "U$2") (pin "VIN8") (pinfunction "VIN8_VIN8") (pintype "bidirectional"))
      (node (ref "U$2") (pin "VIN9") (pinfunction "VIN9_VIN9") (pintype "bidirectional"))
      (node (ref "VIN") (pin "1") (pinfunction "1_1") (pintype "passive"))
    )
    (net (code "13") (name "VOUT") (class "Default")
      (node (ref "C10") (pin "1") (pinfunction "1_1") (pintype "passive"))
      (node (ref "C19") (pin "1") (pinfunction "1_1") (pintype "passive"))
      (node (ref "C20") (pin "1") (pinfunction "1_1") (pintype "passive"))
      (node (ref "C21") (pin "1") (pinfunction "1_1") (pintype "passive"))
      (node (ref "C22") (pin "1") (pinfunction "1_1") (pintype "passive"))
      (node (ref "C7") (pin "1") (pinfunction "1_1") (pintype "passive"))
      (node (ref "C8") (pin "1") (pinfunction "1_1") (pintype "passive"))
      (node (ref "C9") (pin "1") (pinfunction "1_1") (pintype "passive"))
      (node (ref "J2") (pin "1") (pinfunction "1_1") (pintype "passive"))
      (node (ref "R5") (pin "1") (pinfunction "1_1") (pintype "passive"))
      (node (ref "U$2") (pin "VOUT1") (pinfunction "VOUT1_VOUT1") (pintype "bidirectional"))
      (node (ref "U$2") (pin "VOUT2") (pinfunction "VOUT2_VOUT2") (pintype "bidirectional"))
      (node (ref "VOUT1=3.6V") (pin "1") (pinfunction "1_1") (pintype "passive"))
    )
    (net (code "14") (name "VOUT2") (class "Default")
      (node (ref "C11") (pin "1") (pinfunction "1_1") (pintype "passive"))
      (node (ref "C12") (pin "1") (pinfunction "1_1") (pintype "passive"))
      (node (ref "C13") (pin "1") (pinfunction "1_1") (pintype "passive"))
      (node (ref "C14") (pin "1") (pinfunction "1_1") (pintype "passive"))
      (node (ref "C23") (pin "1") (pinfunction "1_1") (pintype "passive"))
      (node (ref "C24") (pin "1") (pinfunction "1_1") (pintype "passive"))
      (node (ref "C25") (pin "1") (pinfunction "1_1") (pintype "passive"))
      (node (ref "C26") (pin "1") (pinfunction "1_1") (pintype "passive"))
      (node (ref "J4") (pin "1") (pinfunction "1_1") (pintype "passive"))
      (node (ref "R6") (pin "1") (pinfunction "1_1") (pintype "passive"))
      (node (ref "U$1") (pin "VOUT1") (pinfunction "VOUT1_VOUT1") (pintype "bidirectional"))
      (node (ref "U$1") (pin "VOUT2") (pinfunction "VOUT2_VOUT2") (pintype "bidirectional"))
      (node (ref "VOUT2=2.2V") (pin "1") (pinfunction "1_1") (pintype "passive"))
    )
    (net (code "15") (name "VS1") (class "Default")
      (node (ref "J1") (pin "1") (pinfunction "1_1") (pintype "passive"))
      (node (ref "U$2") (pin "VS11") (pinfunction "VS11_VS11") (pintype "bidirectional"))
      (node (ref "U$2") (pin "VS110") (pinfunction "VS110_VS110") (pintype "bidirectional"))
      (node (ref "U$2") (pin "VS12") (pinfunction "VS12_VS12") (pintype "bidirectional"))
      (node (ref "U$2") (pin "VS13") (pinfunction "VS13_VS13") (pintype "bidirectional"))
      (node (ref "U$2") (pin "VS14") (pinfunction "VS14_VS14") (pintype "bidirectional"))
      (node (ref "U$2") (pin "VS15") (pinfunction "VS15_VS15") (pintype "bidirectional"))
      (node (ref "U$2") (pin "VS16") (pinfunction "VS16_VS16") (pintype "bidirectional"))
      (node (ref "U$2") (pin "VS17") (pinfunction "VS17_VS17") (pintype "bidirectional"))
      (node (ref "U$2") (pin "VS18") (pinfunction "VS18_VS18") (pintype "bidirectional"))
      (node (ref "U$2") (pin "VS19") (pinfunction "VS19_VS19") (pintype "bidirectional"))
    )
    (net (code "16") (name "VS12") (class "Default")
      (node (ref "J3") (pin "1") (pinfunction "1_1") (pintype "passive"))
      (node (ref "U$1") (pin "VS11") (pinfunction "VS11_VS11") (pintype "bidirectional"))
      (node (ref "U$1") (pin "VS110") (pinfunction "VS110_VS110") (pintype "bidirectional"))
      (node (ref "U$1") (pin "VS12") (pinfunction "VS12_VS12") (pintype "bidirectional"))
      (node (ref "U$1") (pin "VS13") (pinfunction "VS13_VS13") (pintype "bidirectional"))
      (node (ref "U$1") (pin "VS14") (pinfunction "VS14_VS14") (pintype "bidirectional"))
      (node (ref "U$1") (pin "VS15") (pinfunction "VS15_VS15") (pintype "bidirectional"))
      (node (ref "U$1") (pin "VS16") (pinfunction "VS16_VS16") (pintype "bidirectional"))
      (node (ref "U$1") (pin "VS17") (pinfunction "VS17_VS17") (pintype "bidirectional"))
      (node (ref "U$1") (pin "VS18") (pinfunction "VS18_VS18") (pintype "bidirectional"))
      (node (ref "U$1") (pin "VS19") (pinfunction "VS19_VS19") (pintype "bidirectional"))
    )
    (net (code "17") (name "unconnected-(U$1-PadEAO)") (class "Default")
      (node (ref "U$1") (pin "EAO") (pinfunction "EAO_EAO") (pintype "bidirectional"))
    )
    (net (code "18") (name "unconnected-(U$1-PadEN)") (class "Default")
      (node (ref "U$1") (pin "EN") (pinfunction "EN_EN") (pintype "bidirectional"))
    )
    (net (code "19") (name "unconnected-(U$1-PadPWRGO)") (class "Default")
      (node (ref "U$1") (pin "PWRGO") (pinfunction "PWRGO_PWRGO") (pintype "bidirectional"))
    )
    (net (code "20") (name "unconnected-(U$1-PadSYNC0)") (class "Default")
      (node (ref "U$1") (pin "SYNC0") (pinfunction "SYNC0_SYNC0") (pintype "bidirectional"))
    )
    (net (code "21") (name "unconnected-(U$1-PadTRK)") (class "Default")
      (node (ref "U$1") (pin "TRK") (pinfunction "TRK_TRK") (pintype "bidirectional"))
    )
    (net (code "22") (name "unconnected-(U$1-PadVDR)") (class "Default")
      (node (ref "U$1") (pin "VDR") (pinfunction "VDR_VDR") (pintype "bidirectional"))
    )
    (net (code "23") (name "unconnected-(U$2-PadEAO)") (class "Default")
      (node (ref "U$2") (pin "EAO") (pinfunction "EAO_EAO") (pintype "bidirectional"))
    )
    (net (code "24") (name "unconnected-(U$2-PadEN)") (class "Default")
      (node (ref "U$2") (pin "EN") (pinfunction "EN_EN") (pintype "bidirectional"))
    )
    (net (code "25") (name "unconnected-(U$2-PadPWRGO)") (class "Default")
      (node (ref "U$2") (pin "PWRGO") (pinfunction "PWRGO_PWRGO") (pintype "bidirectional"))
    )
    (net (code "26") (name "unconnected-(U$2-PadSYNC0)") (class "Default")
      (node (ref "U$2") (pin "SYNC0") (pinfunction "SYNC0_SYNC0") (pintype "bidirectional"))
    )
    (net (code "27") (name "unconnected-(U$2-PadTRK)") (class "Default")
      (node (ref "U$2") (pin "TRK") (pinfunction "TRK_TRK") (pintype "bidirectional"))
    )
    (net (code "28") (name "unconnected-(U$2-PadVDR)") (class "Default")
      (node (ref "U$2") (pin "VDR") (pinfunction "VDR_VDR") (pintype "bidirectional"))
    )
  )
)
